# POWER.net
KiCad netlist of a schematic drawn in Altium Designer
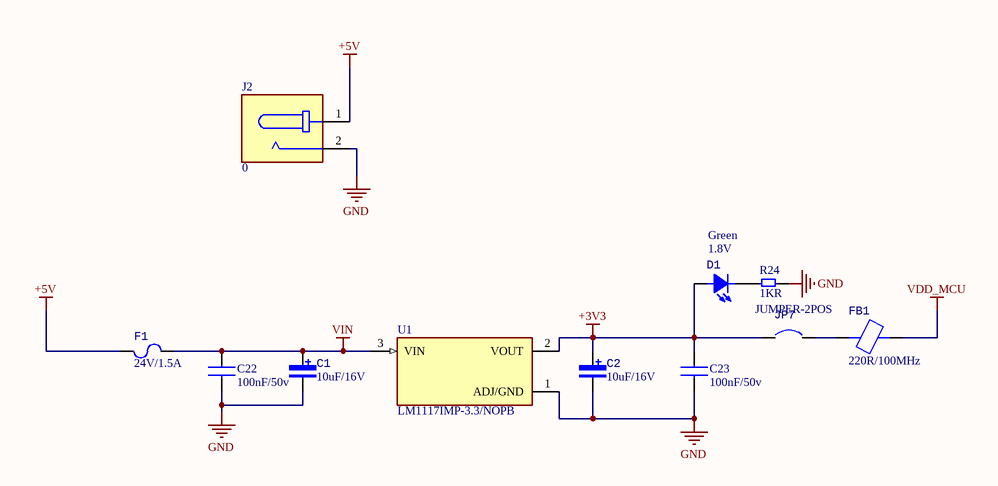
[diagram p0: POWER.SchDoc]

(export (version "E")
  (design (tool "Eeschema 10.0.6"))
  (components
    (comp (ref "C1")
      (value "10uF/16V")
      (footprint "CAP_Tantalum_3216")
      (description "Tụ Tantalum 10uF 16V 1206 TAJA106K016RNJ")
      (libsource (lib "Database_Libs1") (part "CAP-TAN"))
    )
    (comp (ref "C2")
      (value "10uF/16V")
      (footprint "CAP_Tantalum_3216")
      (description "Tụ Tantalum 10uF 16V 1206 TAJA106K016RNJ")
      (libsource (lib "Database_Libs1") (part "CAP-TAN"))
    )
    (comp (ref "C22") (value "100nF/50v") (footprint "CAP-CER-0805") (libsource (lib "ID") (part "CAP-CER")))
    (comp (ref "C23") (value "100nF/50v") (footprint "CAP-CER-0805") (libsource (lib "ID") (part "CAP-CER")))
    (comp (ref "D1")
      (value "1.8V")
      (footprint "LED_SMD_0805_GREEN")
      (description "LED Xanh Lá 0805 Dán SMD Trong Suốt Harvatek")
      (fields (field (name "MFR# #") "Green"))
      (libsource (lib "Database_Libs1") (part "LED"))
    )
    (comp (ref "F1")
      (value "24V/1.5A")
      (footprint "FUSER_MF-MSMF150/24X-2")
      (description "MF-MSMF150/24X-2 Cầu Chì Tự Phục Hồi 1812 24V 1.5A")
      (libsource (lib "Database_Libs1") (part "FUSE"))
    )
    (comp (ref "FB1")
      (value "220R/100MHz")
      (footprint "FERRITE-0603")
      (libsource (lib "Database_Libs1") (part "FERRITE-BEAD"))
    )
    (comp (ref "J2")
      (value "0")
      (footprint "CUI_PJ-037AH")
      (description "2.0 x 6.5 mm, 5.0 A, Horizontal, Through Hole, Dc Power Jack Connector")
      (fields (field (name "MF") "Same Sky") (field (name "MP") "PJ-037AH"))
      (libsource (lib "ID") (part "JACK DC"))
    )
    (comp (ref "JP7")
      (value "JUMPER-2POS")
      (footprint "JUMPER-2POS-2.54")
      (fields (field (name "MFR# #") "JUMPER-2POS"))
      (libsource (lib "Database_Libs1") (part "JUMPER-2POS"))
    )
    (comp (ref "R24") (value "1KR") (footprint "RES-SMD-0805") (libsource (lib "ID") (part "RES_SMD")))
    (comp (ref "U1")
      (value "LM1117IMP-3.3/NOPB")
      (footprint "LM1117IMP-3.3/NOPB")
      (description "800-mA 15-V linear voltage regulator")
      (fields (field (name "MF") "Texas Instruments"))
      (libsource (lib "ID") (part "LDO"))
    )
  )
  (nets
    (net (code "1") (name "+3V3") (class "Default")
      (node (ref "C2") (pin "1") (pinfunction "1_1") (pintype "passive"))
      (node (ref "C23") (pin "2") (pinfunction "2_2") (pintype "passive"))
      (node (ref "D1") (pin "1") (pinfunction "A_1") (pintype "passive"))
      (node (ref "JP7") (pin "1") (pinfunction "1_1") (pintype "passive"))
      (node (ref "U1") (pin "2") (pinfunction "VOUT_2") (pintype "power_in"))
    )
    (net (code "2") (name "+5V") (class "Default")
      (node (ref "F1") (pin "2") (pinfunction "2_2") (pintype "passive"))
      (node (ref "J2") (pin "1") (pinfunction "1_1") (pintype "passive"))
    )
    (net (code "3") (name "GND") (class "Default")
      (node (ref "C1") (pin "2") (pinfunction "2_2") (pintype "passive"))
      (node (ref "C2") (pin "2") (pinfunction "2_2") (pintype "passive"))
      (node (ref "C22") (pin "1") (pinfunction "1_1") (pintype "passive"))
      (node (ref "C23") (pin "1") (pinfunction "1_1") (pintype "passive"))
      (node (ref "J2") (pin "2") (pinfunction "2_2") (pintype "power_in"))
      (node (ref "R24") (pin "2") (pinfunction "2_2") (pintype "passive"))
      (node (ref "U1") (pin "1") (pinfunction "ADJ/GND_1") (pintype "power_in"))
    )
    (net (code "4") (name "Net-(D1-K)") (class "Default")
      (node (ref "D1") (pin "2") (pinfunction "K_2") (pintype "passive"))
      (node (ref "R24") (pin "1") (pinfunction "1_1") (pintype "passive"))
    )
    (net (code "5") (name "Net-(FB1-Pad1)") (class "Default")
      (node (ref "FB1") (pin "1") (pinfunction "1_1") (pintype "passive"))
      (node (ref "JP7") (pin "2") (pinfunction "2_2") (pintype "passive"))
    )
    (net (code "6") (name "VDD_MCU") (class "Default")
      (node (ref "FB1") (pin "2") (pinfunction "2_2") (pintype "passive"))
    )
    (net (code "7") (name "VIN") (class "Default")
      (node (ref "C1") (pin "1") (pinfunction "1_1") (pintype "passive"))
      (node (ref "C22") (pin "2") (pinfunction "2_2") (pintype "passive"))
      (node (ref "F1") (pin "1") (pinfunction "1_1") (pintype "passive"))
      (node (ref "U1") (pin "3") (pinfunction "VIN_3") (pintype "input"))
    )
  )
)
